# DEP_REVC_0.net
KiCad netlist of a schematic drawn in Altium Designer
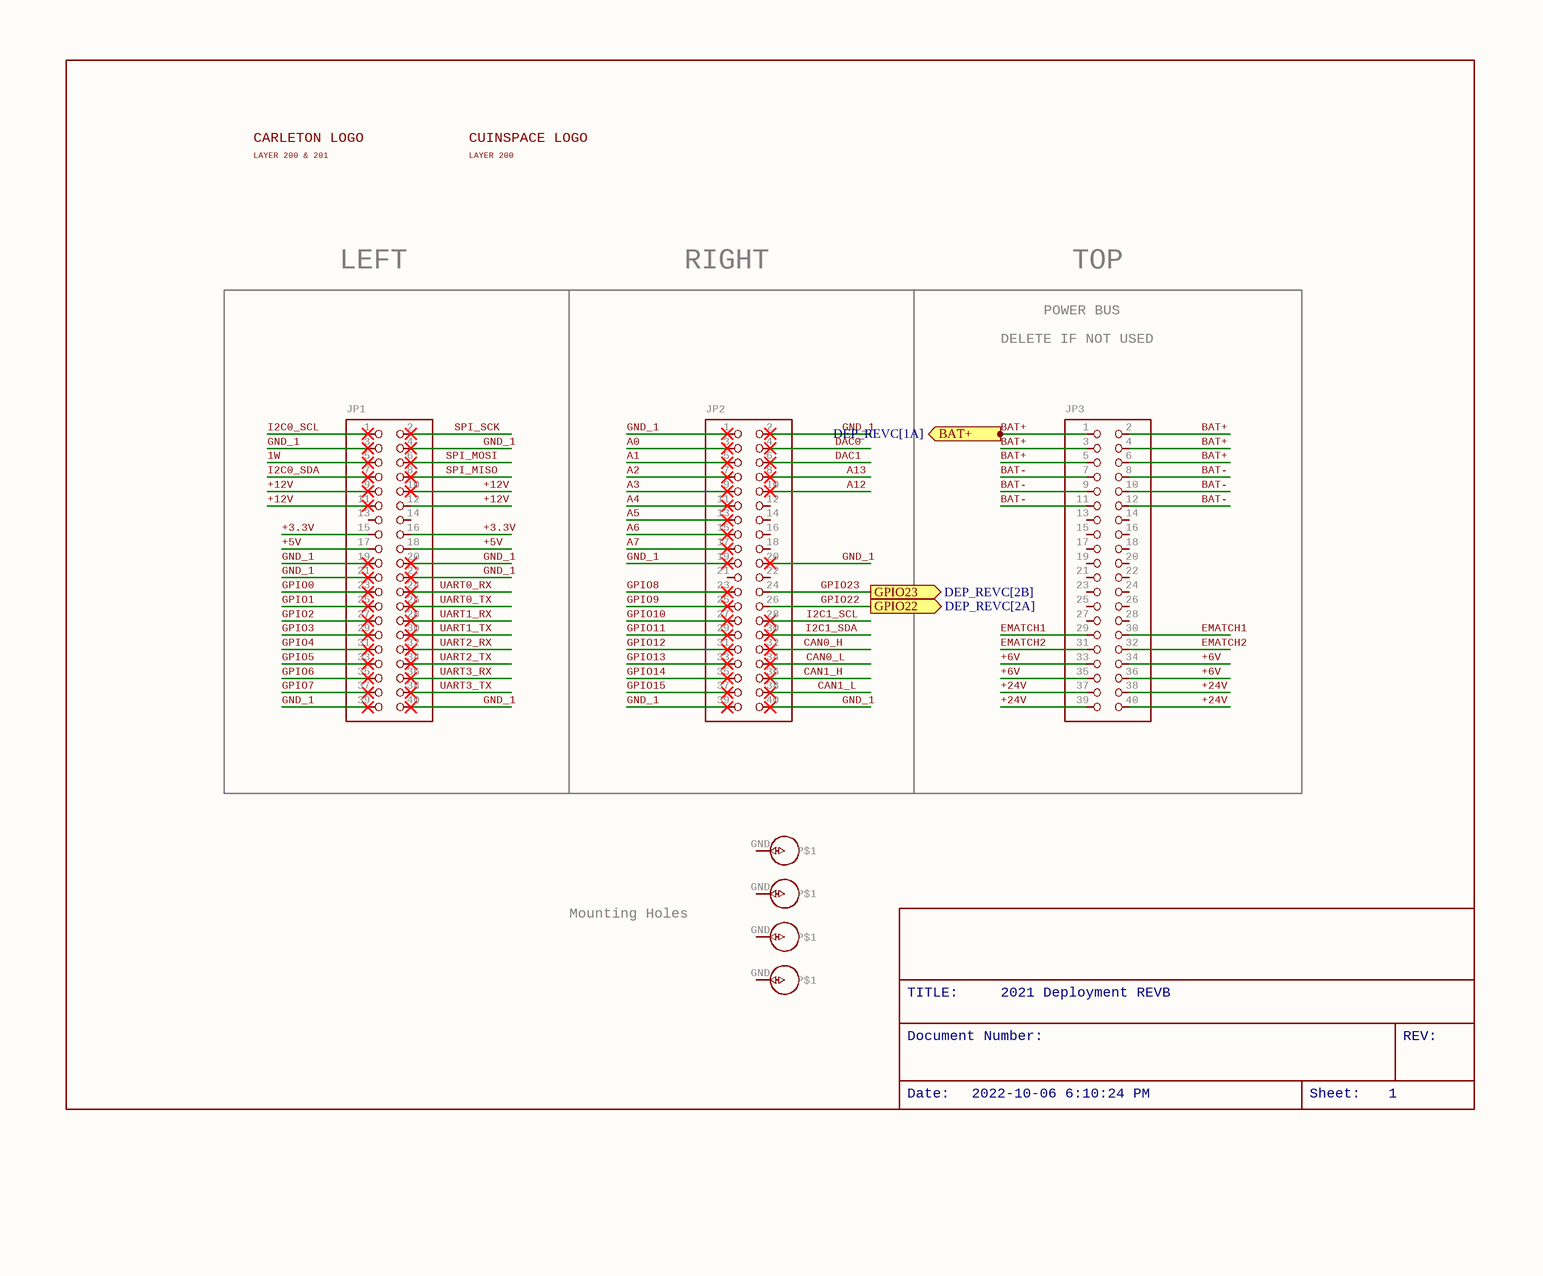
[diagram p0: DEP_REVC_0.SchDoc]

(export (version "E")
  (design (tool "Eeschema 10.0.6"))
  (components
    (comp (ref "$$U$1")
      (value "PS/104-MOUNTING-HOLE")
      (footprint "PC/104-MOUNTING-HOLE")
      (description "Mounting hole for PC/104 board.")
      (libsource (lib "CU inSpace 2019 Parts") (part "PS/104-MOUNTING-HOLE"))
    )
    (comp (ref "JP1")
      (value "PINHD-2X20")
      (footprint "2X20")
      (description "PIN HEADER")
      (fields (field (name "LIBRARYNAME") "pinhead"))
      (libsource (lib "pinhead") (part "PINHD-2X20"))
    )
    (comp (ref "JP2")
      (value "PINHD-2X20")
      (footprint "2X20")
      (description "PIN HEADER")
      (fields (field (name "LIBRARYNAME") "pinhead"))
      (libsource (lib "pinhead") (part "PINHD-2X20"))
    )
    (comp (ref "JP3")
      (value "PINHD-2X20")
      (footprint "2X20")
      (description "PIN HEADER")
      (fields (field (name "LIBRARYNAME") "pinhead"))
      (libsource (lib "pinhead") (part "PINHD-2X20"))
    )
    (comp (ref "U$1")
      (value "PS/104-MOUNTING-HOLE")
      (footprint "PC/104-MOUNTING-HOLE")
      (description "Mounting hole for PC/104 board.")
      (libsource (lib "CU inSpace 2019 Parts") (part "PS/104-MOUNTING-HOLE"))
    )
    (comp (ref "U$2")
      (value "PS/104-MOUNTING-HOLE")
      (footprint "PC/104-MOUNTING-HOLE")
      (description "Mounting hole for PC/104 board.")
      (libsource (lib "CU inSpace 2019 Parts") (part "PS/104-MOUNTING-HOLE"))
    )
    (comp (ref "U$3")
      (value "PS/104-MOUNTING-HOLE")
      (footprint "PC/104-MOUNTING-HOLE")
      (description "Mounting hole for PC/104 board.")
      (libsource (lib "CU inSpace 2019 Parts") (part "PS/104-MOUNTING-HOLE"))
    )
    (comp (ref "U$4")
      (value "CARLETON3CM")
      (footprint "CARLETONU_3CM")
      (fields
        (field (name "CARLETONLOGO") "CARLETON LOGO")
        (field (name "LAYER200&201") "LAYER 200 & 201")
        (field (name "LIBRARYNAME") "Logos")
      )
      (libsource (lib "Logos") (part "CARLETON3CM"))
    )
    (comp (ref "U$6")
      (value "INSPACE3CM_L")
      (footprint "INSPACE_3CM_LETTERS")
      (fields
        (field (name "CUINSPACELOGO") "CUINSPACE LOGO")
        (field (name "LAYER200") "LAYER 200")
        (field (name "LIBRARYNAME") "Logos")
      )
      (libsource (lib "Logos") (part "INSPACE3CM_L"))
    )
  )
  (nets
    (net (code "1") (name "/+3.3V") (class "Default")
      (node (ref "JP1") (pin "15") (pinfunction "15_15") (pintype "passive"))
      (node (ref "JP1") (pin "16") (pinfunction "16_16") (pintype "passive"))
    )
    (net (code "2") (name "/+5V") (class "Default")
      (node (ref "JP1") (pin "17") (pinfunction "17_17") (pintype "passive"))
      (node (ref "JP1") (pin "18") (pinfunction "18_18") (pintype "passive"))
    )
    (net (code "3") (name "/+6V") (class "Default")
      (node (ref "JP3") (pin "33") (pinfunction "33_33") (pintype "passive"))
      (node (ref "JP3") (pin "34") (pinfunction "34_34") (pintype "passive"))
      (node (ref "JP3") (pin "35") (pinfunction "35_35") (pintype "passive"))
      (node (ref "JP3") (pin "36") (pinfunction "36_36") (pintype "passive"))
    )
    (net (code "4") (name "/+12V") (class "Default")
      (node (ref "JP1") (pin "10") (pinfunction "10_10") (pintype "passive"))
      (node (ref "JP1") (pin "11") (pinfunction "11_11") (pintype "passive"))
      (node (ref "JP1") (pin "12") (pinfunction "12_12") (pintype "passive"))
      (node (ref "JP1") (pin "9") (pinfunction "9_9") (pintype "passive"))
    )
    (net (code "5") (name "/+24V") (class "Default")
      (node (ref "JP3") (pin "37") (pinfunction "37_37") (pintype "passive"))
      (node (ref "JP3") (pin "38") (pinfunction "38_38") (pintype "passive"))
      (node (ref "JP3") (pin "39") (pinfunction "39_39") (pintype "passive"))
      (node (ref "JP3") (pin "40") (pinfunction "40_40") (pintype "passive"))
    )
    (net (code "6") (name "/1W") (class "Default")
      (node (ref "JP1") (pin "5") (pinfunction "5_5") (pintype "passive+no_connect"))
    )
    (net (code "7") (name "/A0") (class "Default")
      (node (ref "JP2") (pin "3") (pinfunction "3_3") (pintype "passive+no_connect"))
    )
    (net (code "8") (name "/A1") (class "Default")
      (node (ref "JP2") (pin "5") (pinfunction "5_5") (pintype "passive+no_connect"))
    )
    (net (code "9") (name "/A2") (class "Default")
      (node (ref "JP2") (pin "7") (pinfunction "7_7") (pintype "passive+no_connect"))
    )
    (net (code "10") (name "/A3") (class "Default")
      (node (ref "JP2") (pin "9") (pinfunction "9_9") (pintype "passive+no_connect"))
    )
    (net (code "11") (name "/A4") (class "Default")
      (node (ref "JP2") (pin "11") (pinfunction "11_11") (pintype "passive+no_connect"))
    )
    (net (code "12") (name "/A5") (class "Default")
      (node (ref "JP2") (pin "13") (pinfunction "13_13") (pintype "passive+no_connect"))
    )
    (net (code "13") (name "/A6") (class "Default")
      (node (ref "JP2") (pin "15") (pinfunction "15_15") (pintype "passive+no_connect"))
    )
    (net (code "14") (name "/A7") (class "Default")
      (node (ref "JP2") (pin "17") (pinfunction "17_17") (pintype "passive+no_connect"))
    )
    (net (code "15") (name "/A12") (class "Default")
      (node (ref "JP2") (pin "10") (pinfunction "10_10") (pintype "passive+no_connect"))
    )
    (net (code "16") (name "/A13") (class "Default")
      (node (ref "JP2") (pin "8") (pinfunction "8_8") (pintype "passive+no_connect"))
    )
    (net (code "17") (name "/BAT+") (class "Default")
      (node (ref "JP3") (pin "1") (pinfunction "1_1") (pintype "passive"))
      (node (ref "JP3") (pin "2") (pinfunction "2_2") (pintype "passive"))
      (node (ref "JP3") (pin "3") (pinfunction "3_3") (pintype "passive"))
      (node (ref "JP3") (pin "4") (pinfunction "4_4") (pintype "passive"))
      (node (ref "JP3") (pin "5") (pinfunction "5_5") (pintype "passive"))
      (node (ref "JP3") (pin "6") (pinfunction "6_6") (pintype "passive"))
    )
    (net (code "18") (name "/BAT-") (class "Default")
      (node (ref "JP3") (pin "10") (pinfunction "10_10") (pintype "passive"))
      (node (ref "JP3") (pin "11") (pinfunction "11_11") (pintype "passive"))
      (node (ref "JP3") (pin "12") (pinfunction "12_12") (pintype "passive"))
      (node (ref "JP3") (pin "7") (pinfunction "7_7") (pintype "passive"))
      (node (ref "JP3") (pin "8") (pinfunction "8_8") (pintype "passive"))
      (node (ref "JP3") (pin "9") (pinfunction "9_9") (pintype "passive"))
    )
    (net (code "19") (name "/CAN0_H") (class "Default")
      (node (ref "JP2") (pin "32") (pinfunction "32_32") (pintype "passive+no_connect"))
    )
    (net (code "20") (name "/CAN0_L") (class "Default")
      (node (ref "JP2") (pin "34") (pinfunction "34_34") (pintype "passive+no_connect"))
    )
    (net (code "21") (name "/CAN1_H") (class "Default")
      (node (ref "JP2") (pin "36") (pinfunction "36_36") (pintype "passive+no_connect"))
    )
    (net (code "22") (name "/CAN1_L") (class "Default")
      (node (ref "JP2") (pin "38") (pinfunction "38_38") (pintype "passive+no_connect"))
    )
    (net (code "23") (name "/DAC0") (class "Default")
      (node (ref "JP2") (pin "4") (pinfunction "4_4") (pintype "passive+no_connect"))
    )
    (net (code "24") (name "/DAC1") (class "Default")
      (node (ref "JP2") (pin "6") (pinfunction "6_6") (pintype "passive+no_connect"))
    )
    (net (code "25") (name "/EMATCH1") (class "Default")
      (node (ref "JP3") (pin "29") (pinfunction "29_29") (pintype "passive"))
      (node (ref "JP3") (pin "30") (pinfunction "30_30") (pintype "passive"))
    )
    (net (code "26") (name "/EMATCH2") (class "Default")
      (node (ref "JP3") (pin "31") (pinfunction "31_31") (pintype "passive"))
      (node (ref "JP3") (pin "32") (pinfunction "32_32") (pintype "passive"))
    )
    (net (code "27") (name "/GND_1") (class "Default")
      (node (ref "JP1") (pin "19") (pinfunction "19_19") (pintype "passive"))
      (node (ref "JP1") (pin "20") (pinfunction "20_20") (pintype "passive"))
      (node (ref "JP1") (pin "21") (pinfunction "21_21") (pintype "passive"))
      (node (ref "JP1") (pin "22") (pinfunction "22_22") (pintype "passive"))
      (node (ref "JP1") (pin "3") (pinfunction "3_3") (pintype "passive"))
      (node (ref "JP1") (pin "39") (pinfunction "39_39") (pintype "passive"))
      (node (ref "JP1") (pin "4") (pinfunction "4_4") (pintype "passive"))
      (node (ref "JP1") (pin "40") (pinfunction "40_40") (pintype "passive"))
      (node (ref "JP2") (pin "1") (pinfunction "1_1") (pintype "passive"))
      (node (ref "JP2") (pin "19") (pinfunction "19_19") (pintype "passive"))
      (node (ref "JP2") (pin "2") (pinfunction "2_2") (pintype "passive"))
      (node (ref "JP2") (pin "20") (pinfunction "20_20") (pintype "passive"))
      (node (ref "JP2") (pin "39") (pinfunction "39_39") (pintype "passive"))
      (node (ref "JP2") (pin "40") (pinfunction "40_40") (pintype "passive"))
    )
    (net (code "28") (name "/GPIO0") (class "Default")
      (node (ref "JP1") (pin "23") (pinfunction "23_23") (pintype "passive+no_connect"))
    )
    (net (code "29") (name "/GPIO1") (class "Default")
      (node (ref "JP1") (pin "25") (pinfunction "25_25") (pintype "passive+no_connect"))
    )
    (net (code "30") (name "/GPIO2") (class "Default")
      (node (ref "JP1") (pin "27") (pinfunction "27_27") (pintype "passive+no_connect"))
    )
    (net (code "31") (name "/GPIO3") (class "Default")
      (node (ref "JP1") (pin "29") (pinfunction "29_29") (pintype "passive+no_connect"))
    )
    (net (code "32") (name "/GPIO4") (class "Default")
      (node (ref "JP1") (pin "31") (pinfunction "31_31") (pintype "passive+no_connect"))
    )
    (net (code "33") (name "/GPIO5") (class "Default")
      (node (ref "JP1") (pin "33") (pinfunction "33_33") (pintype "passive+no_connect"))
    )
    (net (code "34") (name "/GPIO6") (class "Default")
      (node (ref "JP1") (pin "35") (pinfunction "35_35") (pintype "passive+no_connect"))
    )
    (net (code "35") (name "/GPIO7") (class "Default")
      (node (ref "JP1") (pin "37") (pinfunction "37_37") (pintype "passive+no_connect"))
    )
    (net (code "36") (name "/GPIO8") (class "Default")
      (node (ref "JP2") (pin "23") (pinfunction "23_23") (pintype "passive+no_connect"))
    )
    (net (code "37") (name "/GPIO9") (class "Default")
      (node (ref "JP2") (pin "25") (pinfunction "25_25") (pintype "passive+no_connect"))
    )
    (net (code "38") (name "/GPIO10") (class "Default")
      (node (ref "JP2") (pin "27") (pinfunction "27_27") (pintype "passive+no_connect"))
    )
    (net (code "39") (name "/GPIO11") (class "Default")
      (node (ref "JP2") (pin "29") (pinfunction "29_29") (pintype "passive+no_connect"))
    )
    (net (code "40") (name "/GPIO12") (class "Default")
      (node (ref "JP2") (pin "31") (pinfunction "31_31") (pintype "passive+no_connect"))
    )
    (net (code "41") (name "/GPIO13") (class "Default")
      (node (ref "JP2") (pin "33") (pinfunction "33_33") (pintype "passive+no_connect"))
    )
    (net (code "42") (name "/GPIO14") (class "Default")
      (node (ref "JP2") (pin "35") (pinfunction "35_35") (pintype "passive+no_connect"))
    )
    (net (code "43") (name "/GPIO15") (class "Default")
      (node (ref "JP2") (pin "37") (pinfunction "37_37") (pintype "passive+no_connect"))
    )
    (net (code "44") (name "/GPIO22") (class "Default")
      (node (ref "JP2") (pin "26") (pinfunction "26_26") (pintype "passive"))
    )
    (net (code "45") (name "/GPIO23") (class "Default")
      (node (ref "JP2") (pin "24") (pinfunction "24_24") (pintype "passive"))
    )
    (net (code "46") (name "/I2C0_SCL") (class "Default")
      (node (ref "JP1") (pin "1") (pinfunction "1_1") (pintype "passive+no_connect"))
    )
    (net (code "47") (name "/I2C0_SDA") (class "Default")
      (node (ref "JP1") (pin "7") (pinfunction "7_7") (pintype "passive+no_connect"))
    )
    (net (code "48") (name "/I2C1_SCL") (class "Default")
      (node (ref "JP2") (pin "28") (pinfunction "28_28") (pintype "passive+no_connect"))
    )
    (net (code "49") (name "/I2C1_SDA") (class "Default")
      (node (ref "JP2") (pin "30") (pinfunction "30_30") (pintype "passive+no_connect"))
    )
    (net (code "50") (name "/SPI_MISO") (class "Default")
      (node (ref "JP1") (pin "8") (pinfunction "8_8") (pintype "passive+no_connect"))
    )
    (net (code "51") (name "/SPI_MOSI") (class "Default")
      (node (ref "JP1") (pin "6") (pinfunction "6_6") (pintype "passive+no_connect"))
    )
    (net (code "52") (name "/SPI_SCK") (class "Default")
      (node (ref "JP1") (pin "2") (pinfunction "2_2") (pintype "passive+no_connect"))
    )
    (net (code "53") (name "/UART0_RX") (class "Default")
      (node (ref "JP1") (pin "24") (pinfunction "24_24") (pintype "passive+no_connect"))
    )
    (net (code "54") (name "/UART0_TX") (class "Default")
      (node (ref "JP1") (pin "26") (pinfunction "26_26") (pintype "passive+no_connect"))
    )
    (net (code "55") (name "/UART1_RX") (class "Default")
      (node (ref "JP1") (pin "28") (pinfunction "28_28") (pintype "passive+no_connect"))
    )
    (net (code "56") (name "/UART1_TX") (class "Default")
      (node (ref "JP1") (pin "30") (pinfunction "30_30") (pintype "passive+no_connect"))
    )
    (net (code "57") (name "/UART2_RX") (class "Default")
      (node (ref "JP1") (pin "32") (pinfunction "32_32") (pintype "passive+no_connect"))
    )
    (net (code "58") (name "/UART2_TX") (class "Default")
      (node (ref "JP1") (pin "34") (pinfunction "34_34") (pintype "passive+no_connect"))
    )
    (net (code "59") (name "/UART3_RX") (class "Default")
      (node (ref "JP1") (pin "36") (pinfunction "36_36") (pintype "passive+no_connect"))
    )
    (net (code "60") (name "/UART3_TX") (class "Default")
      (node (ref "JP1") (pin "38") (pinfunction "38_38") (pintype "passive+no_connect"))
    )
    (net (code "61") (name "unconnected-($$U$1-P$1-PadGND)") (class "Default")
      (node (ref "$$U$1") (pin "GND") (pinfunction "P$1_GND") (pintype "bidirectional"))
    )
    (net (code "62") (name "unconnected-(JP1-Pad13)") (class "Default")
      (node (ref "JP1") (pin "13") (pinfunction "13_13") (pintype "passive"))
    )
    (net (code "63") (name "unconnected-(JP1-Pad14)") (class "Default")
      (node (ref "JP1") (pin "14") (pinfunction "14_14") (pintype "passive"))
    )
    (net (code "64") (name "unconnected-(JP2-Pad12)") (class "Default")
      (node (ref "JP2") (pin "12") (pinfunction "12_12") (pintype "passive"))
    )
    (net (code "65") (name "unconnected-(JP2-Pad14)") (class "Default")
      (node (ref "JP2") (pin "14") (pinfunction "14_14") (pintype "passive"))
    )
    (net (code "66") (name "unconnected-(JP2-Pad16)") (class "Default")
      (node (ref "JP2") (pin "16") (pinfunction "16_16") (pintype "passive"))
    )
    (net (code "67") (name "unconnected-(JP2-Pad18)") (class "Default")
      (node (ref "JP2") (pin "18") (pinfunction "18_18") (pintype "passive"))
    )
    (net (code "68") (name "unconnected-(JP2-Pad21)") (class "Default")
      (node (ref "JP2") (pin "21") (pinfunction "21_21") (pintype "passive"))
    )
    (net (code "69") (name "unconnected-(JP2-Pad22)") (class "Default")
      (node (ref "JP2") (pin "22") (pinfunction "22_22") (pintype "passive"))
    )
    (net (code "70") (name "unconnected-(JP3-Pad13)") (class "Default")
      (node (ref "JP3") (pin "13") (pinfunction "13_13") (pintype "passive"))
    )
    (net (code "71") (name "unconnected-(JP3-Pad14)") (class "Default")
      (node (ref "JP3") (pin "14") (pinfunction "14_14") (pintype "passive"))
    )
    (net (code "72") (name "unconnected-(JP3-Pad15)") (class "Default")
      (node (ref "JP3") (pin "15") (pinfunction "15_15") (pintype "passive"))
    )
    (net (code "73") (name "unconnected-(JP3-Pad16)") (class "Default")
      (node (ref "JP3") (pin "16") (pinfunction "16_16") (pintype "passive"))
    )
    (net (code "74") (name "unconnected-(JP3-Pad17)") (class "Default")
      (node (ref "JP3") (pin "17") (pinfunction "17_17") (pintype "passive"))
    )
    (net (code "75") (name "unconnected-(JP3-Pad18)") (class "Default")
      (node (ref "JP3") (pin "18") (pinfunction "18_18") (pintype "passive"))
    )
    (net (code "76") (name "unconnected-(JP3-Pad19)") (class "Default")
      (node (ref "JP3") (pin "19") (pinfunction "19_19") (pintype "passive"))
    )
    (net (code "77") (name "unconnected-(JP3-Pad20)") (class "Default")
      (node (ref "JP3") (pin "20") (pinfunction "20_20") (pintype "passive"))
    )
    (net (code "78") (name "unconnected-(JP3-Pad21)") (class "Default")
      (node (ref "JP3") (pin "21") (pinfunction "21_21") (pintype "passive"))
    )
    (net (code "79") (name "unconnected-(JP3-Pad22)") (class "Default")
      (node (ref "JP3") (pin "22") (pinfunction "22_22") (pintype "passive"))
    )
    (net (code "80") (name "unconnected-(JP3-Pad23)") (class "Default")
      (node (ref "JP3") (pin "23") (pinfunction "23_23") (pintype "passive"))
    )
    (net (code "81") (name "unconnected-(JP3-Pad24)") (class "Default")
      (node (ref "JP3") (pin "24") (pinfunction "24_24") (pintype "passive"))
    )
    (net (code "82") (name "unconnected-(JP3-Pad25)") (class "Default")
      (node (ref "JP3") (pin "25") (pinfunction "25_25") (pintype "passive"))
    )
    (net (code "83") (name "unconnected-(JP3-Pad26)") (class "Default")
      (node (ref "JP3") (pin "26") (pinfunction "26_26") (pintype "passive"))
    )
    (net (code "84") (name "unconnected-(JP3-Pad27)") (class "Default")
      (node (ref "JP3") (pin "27") (pinfunction "27_27") (pintype "passive"))
    )
    (net (code "85") (name "unconnected-(JP3-Pad28)") (class "Default")
      (node (ref "JP3") (pin "28") (pinfunction "28_28") (pintype "passive"))
    )
    (net (code "86") (name "unconnected-(U$1-P$1-PadGND)") (class "Default")
      (node (ref "U$1") (pin "GND") (pinfunction "P$1_GND") (pintype "bidirectional"))
    )
    (net (code "87") (name "unconnected-(U$2-P$1-PadGND)") (class "Default")
      (node (ref "U$2") (pin "GND") (pinfunction "P$1_GND") (pintype "bidirectional"))
    )
    (net (code "88") (name "unconnected-(U$3-P$1-PadGND)") (class "Default")
      (node (ref "U$3") (pin "GND") (pinfunction "P$1_GND") (pintype "bidirectional"))
    )
  )
)
